# Core.net
KiCad netlist of a schematic drawn in Altium Designer
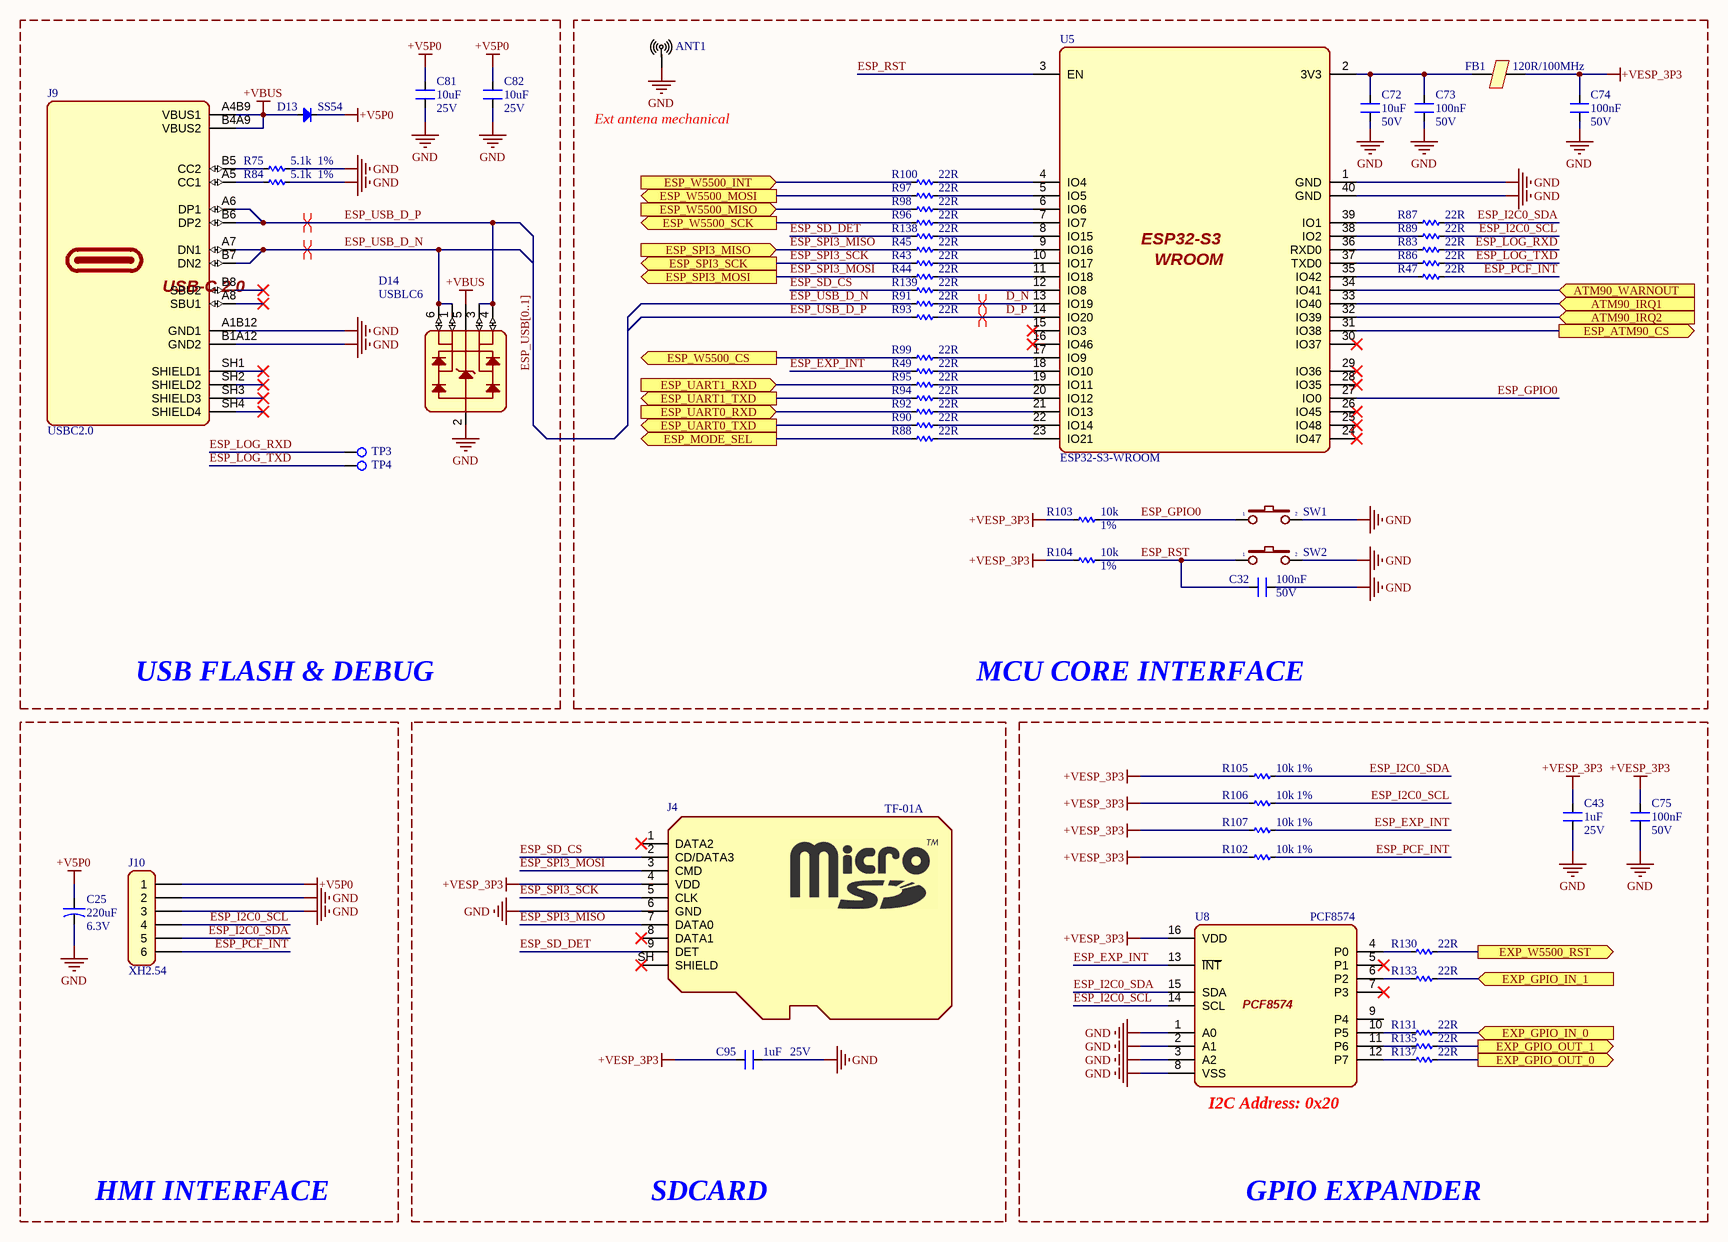
[diagram p0: Core.SchDoc]

(export (version "E")
  (design (tool "Eeschema 10.0.6"))
  (components
    (comp (ref "ANT1")
      (value "Anten")
      (footprint "Library_HUNG:SMA-8.5mm")
      (libsource (lib "Library_HUNG") (part "Anten Mechanical"))
    )
    (comp (ref "C25")
      (value "220uF")
      (footprint "TANT 2312")
      (fields (field (name "RATING") "6.3V"))
      (libsource (lib "Library_HUNG") (part "CN-TANTALUM"))
    )
    (comp (ref "C32")
      (value "100nF")
      (footprint "Library_HUNG:CAP_SMD_0603")
      (fields (field (name "RATING") "50V"))
      (libsource (lib "Library_HUNG") (part "CN"))
    )
    (comp (ref "C43")
      (value "1uF")
      (footprint "Library_HUNG:CAP_SMD_0603")
      (fields (field (name "RATING") "25V"))
      (libsource (lib "Library_HUNG") (part "CN"))
    )
    (comp (ref "C72")
      (value "10uF")
      (footprint "Library_HUNG:CAP_SMD_0805")
      (fields (field (name "RATING") "50V"))
      (libsource (lib "Library_HUNG") (part "CN"))
    )
    (comp (ref "C73")
      (value "100nF")
      (footprint "Library_HUNG:CAP_SMD_0805")
      (fields (field (name "RATING") "50V"))
      (libsource (lib "Library_HUNG") (part "CN"))
    )
    (comp (ref "C74")
      (value "100nF")
      (footprint "Library_HUNG:CAP_SMD_0805")
      (fields (field (name "RATING") "50V"))
      (libsource (lib "Library_HUNG") (part "CN"))
    )
    (comp (ref "C75")
      (value "100nF")
      (footprint "Library_HUNG:CAP_SMD_0603")
      (fields (field (name "RATING") "50V"))
      (libsource (lib "Library_HUNG") (part "CN"))
    )
    (comp (ref "C81")
      (value "10uF")
      (footprint "Library_HUNG:CAP_SMD_0603")
      (fields (field (name "RATING") "25V"))
      (libsource (lib "Library_HUNG") (part "CN"))
    )
    (comp (ref "C82")
      (value "10uF")
      (footprint "Library_HUNG:CAP_SMD_0603")
      (fields (field (name "RATING") "25V"))
      (libsource (lib "Library_HUNG") (part "CN"))
    )
    (comp (ref "C95")
      (value "1uF")
      (footprint "Library_HUNG:CAP_SMD_0603")
      (fields (field (name "RATING") "25V"))
      (libsource (lib "Library_HUNG") (part "CN"))
    )
    (comp (ref "D13")
      (value "SS54")
      (footprint "DIO-SMD-A")
      (description "Default Diode")
      (libsource (lib "Library_HUNG") (part "Diode SMD"))
    )
    (comp (ref "D14")
      (value "USBLC6")
      (footprint "Library_HUNG:SOT23-6")
      (description "TVS DIODE 5.25VWM 17VC SOT23-6")
      (libsource (lib "Library_HUNG") (part "USBLC6"))
    )
    (comp (ref "FB1")
      (value "120R/100MHz")
      (footprint "Ferrite-0805")
      (libsource (lib "Library_HUNG") (part "FERRITE BEAD"))
    )
    (comp (ref "J4")
      (value "TF-01A")
      (footprint "Library_HUNG:TF-01A")
      (libsource (lib "Library_HUNG") (part "SD_Socket"))
    )
    (comp (ref "J9")
      (value "USBC2.0")
      (footprint "Library_HUNG:MOLEX-2171790001")
      (description "USB Type C - Connector, Top-mount SMT, 16pos ¦ Molex Incorporated 217179-0001")
      (libsource (lib "Library_HUNG") (part "USBC-2.0"))
    )
    (comp (ref "J10")
      (value "XH2.54")
      (footprint "XH2.54-6P-TH")
      (libsource (lib "Library_HUNG") (part "Header6"))
    )
    (comp (ref "R43")
      (value "22R")
      (footprint "Library_HUNG:RES_SMD_0603")
      (description "Resistor")
      (fields (field (name "TOLERANCE") "1%"))
      (libsource (lib "Library_HUNG") (part "Res-SMD"))
    )
    (comp (ref "R44")
      (value "22R")
      (footprint "Library_HUNG:RES_SMD_0603")
      (description "Resistor")
      (fields (field (name "TOLERANCE") "1%"))
      (libsource (lib "Library_HUNG") (part "Res-SMD"))
    )
    (comp (ref "R45")
      (value "22R")
      (footprint "Library_HUNG:RES_SMD_0603")
      (description "Resistor")
      (fields (field (name "TOLERANCE") "1%"))
      (libsource (lib "Library_HUNG") (part "Res-SMD"))
    )
    (comp (ref "R47")
      (value "22R")
      (footprint "Library_HUNG:RES_SMD_0603")
      (description "Resistor")
      (fields (field (name "TOLERANCE") "1%"))
      (libsource (lib "Library_HUNG") (part "Res-SMD"))
    )
    (comp (ref "R49")
      (value "22R")
      (footprint "Library_HUNG:RES_SMD_0603")
      (description "Resistor")
      (fields (field (name "TOLERANCE") "1%"))
      (libsource (lib "Library_HUNG") (part "Res-SMD"))
    )
    (comp (ref "R75")
      (value "5.1k")
      (footprint "Library_HUNG:RES_SMD_0603")
      (description "Resistor")
      (fields (field (name "TOLERANCE") "1%"))
      (libsource (lib "Library_HUNG") (part "Res-SMD"))
    )
    (comp (ref "R83")
      (value "22R")
      (footprint "Library_HUNG:RES_SMD_0603")
      (description "Resistor")
      (fields (field (name "TOLERANCE") "1%"))
      (libsource (lib "Library_HUNG") (part "Res-SMD"))
    )
    (comp (ref "R84")
      (value "5.1k")
      (footprint "Library_HUNG:RES_SMD_0603")
      (description "Resistor")
      (fields (field (name "TOLERANCE") "1%"))
      (libsource (lib "Library_HUNG") (part "Res-SMD"))
    )
    (comp (ref "R86")
      (value "22R")
      (footprint "Library_HUNG:RES_SMD_0603")
      (description "Resistor")
      (fields (field (name "TOLERANCE") "1%"))
      (libsource (lib "Library_HUNG") (part "Res-SMD"))
    )
    (comp (ref "R87")
      (value "22R")
      (footprint "Library_HUNG:RES_SMD_0603")
      (description "Resistor")
      (fields (field (name "TOLERANCE") "1%"))
      (libsource (lib "Library_HUNG") (part "Res-SMD"))
    )
    (comp (ref "R88")
      (value "22R")
      (footprint "Library_HUNG:RES_SMD_0603")
      (description "Resistor")
      (fields (field (name "TOLERANCE") "1%"))
      (libsource (lib "Library_HUNG") (part "Res-SMD"))
    )
    (comp (ref "R89")
      (value "22R")
      (footprint "Library_HUNG:RES_SMD_0603")
      (description "Resistor")
      (fields (field (name "TOLERANCE") "1%"))
      (libsource (lib "Library_HUNG") (part "Res-SMD"))
    )
    (comp (ref "R90")
      (value "22R")
      (footprint "Library_HUNG:RES_SMD_0603")
      (description "Resistor")
      (fields (field (name "TOLERANCE") "1%"))
      (libsource (lib "Library_HUNG") (part "Res-SMD"))
    )
    (comp (ref "R91")
      (value "22R")
      (footprint "Library_HUNG:RES_SMD_0603")
      (description "Resistor")
      (fields (field (name "TOLERANCE") "1%"))
      (libsource (lib "Library_HUNG") (part "Res-SMD"))
    )
    (comp (ref "R92")
      (value "22R")
      (footprint "Library_HUNG:RES_SMD_0603")
      (description "Resistor")
      (fields (field (name "TOLERANCE") "1%"))
      (libsource (lib "Library_HUNG") (part "Res-SMD"))
    )
    (comp (ref "R93")
      (value "22R")
      (footprint "Library_HUNG:RES_SMD_0603")
      (description "Resistor")
      (fields (field (name "TOLERANCE") "1%"))
      (libsource (lib "Library_HUNG") (part "Res-SMD"))
    )
    (comp (ref "R94")
      (value "22R")
      (footprint "Library_HUNG:RES_SMD_0603")
      (description "Resistor")
      (fields (field (name "TOLERANCE") "1%"))
      (libsource (lib "Library_HUNG") (part "Res-SMD"))
    )
    (comp (ref "R95")
      (value "22R")
      (footprint "Library_HUNG:RES_SMD_0603")
      (description "Resistor")
      (fields (field (name "TOLERANCE") "1%"))
      (libsource (lib "Library_HUNG") (part "Res-SMD"))
    )
    (comp (ref "R96")
      (value "22R")
      (footprint "Library_HUNG:RES_SMD_0603")
      (description "Resistor")
      (fields (field (name "TOLERANCE") "1%"))
      (libsource (lib "Library_HUNG") (part "Res-SMD"))
    )
    (comp (ref "R97")
      (value "22R")
      (footprint "Library_HUNG:RES_SMD_0603")
      (description "Resistor")
      (fields (field (name "TOLERANCE") "1%"))
      (libsource (lib "Library_HUNG") (part "Res-SMD"))
    )
    (comp (ref "R98")
      (value "22R")
      (footprint "Library_HUNG:RES_SMD_0603")
      (description "Resistor")
      (fields (field (name "TOLERANCE") "1%"))
      (libsource (lib "Library_HUNG") (part "Res-SMD"))
    )
    (comp (ref "R99")
      (value "22R")
      (footprint "Library_HUNG:RES_SMD_0603")
      (description "Resistor")
      (fields (field (name "TOLERANCE") "1%"))
      (libsource (lib "Library_HUNG") (part "Res-SMD"))
    )
    (comp (ref "R100")
      (value "22R")
      (footprint "Library_HUNG:RES_SMD_0603")
      (description "Resistor")
      (fields (field (name "TOLERANCE") "1%"))
      (libsource (lib "Library_HUNG") (part "Res-SMD"))
    )
    (comp (ref "R102")
      (value "10k")
      (footprint "Library_HUNG:RES_SMD_0603")
      (description "Resistor")
      (fields (field (name "TOLERANCE") "1%"))
      (libsource (lib "Library_HUNG") (part "Res-SMD"))
    )
    (comp (ref "R103")
      (value "10k")
      (footprint "Library_HUNG:RES_SMD_0603")
      (description "Resistor")
      (fields (field (name "TOLERANCE") "1%"))
      (libsource (lib "Library_HUNG") (part "Res-SMD"))
    )
    (comp (ref "R104")
      (value "10k")
      (footprint "Library_HUNG:RES_SMD_0603")
      (description "Resistor")
      (fields (field (name "TOLERANCE") "1%"))
      (libsource (lib "Library_HUNG") (part "Res-SMD"))
    )
    (comp (ref "R105")
      (value "10k")
      (footprint "Library_HUNG:RES_SMD_0603")
      (description "Resistor")
      (fields (field (name "TOLERANCE") "1%"))
      (libsource (lib "Library_HUNG") (part "Res-SMD"))
    )
    (comp (ref "R106")
      (value "10k")
      (footprint "Library_HUNG:RES_SMD_0603")
      (description "Resistor")
      (fields (field (name "TOLERANCE") "1%"))
      (libsource (lib "Library_HUNG") (part "Res-SMD"))
    )
    (comp (ref "R107")
      (value "10k")
      (footprint "Library_HUNG:RES_SMD_0603")
      (description "Resistor")
      (fields (field (name "TOLERANCE") "1%"))
      (libsource (lib "Library_HUNG") (part "Res-SMD"))
    )
    (comp (ref "R130")
      (value "22R")
      (footprint "Library_HUNG:RES_SMD_0603")
      (description "Resistor")
      (fields (field (name "TOLERANCE") "1%"))
      (libsource (lib "Library_HUNG") (part "Res-SMD"))
    )
    (comp (ref "R131")
      (value "22R")
      (footprint "Library_HUNG:RES_SMD_0603")
      (description "Resistor")
      (fields (field (name "TOLERANCE") "1%"))
      (libsource (lib "Library_HUNG") (part "Res-SMD"))
    )
    (comp (ref "R133")
      (value "22R")
      (footprint "Library_HUNG:RES_SMD_0603")
      (description "Resistor")
      (fields (field (name "TOLERANCE") "1%"))
      (libsource (lib "Library_HUNG") (part "Res-SMD"))
    )
    (comp (ref "R135")
      (value "22R")
      (footprint "Library_HUNG:RES_SMD_0603")
      (description "Resistor")
      (fields (field (name "TOLERANCE") "1%"))
      (libsource (lib "Library_HUNG") (part "Res-SMD"))
    )
    (comp (ref "R137")
      (value "22R")
      (footprint "Library_HUNG:RES_SMD_0603")
      (description "Resistor")
      (fields (field (name "TOLERANCE") "1%"))
      (libsource (lib "Library_HUNG") (part "Res-SMD"))
    )
    (comp (ref "R138")
      (value "22R")
      (footprint "Library_HUNG:RES_SMD_0603")
      (description "Resistor")
      (fields (field (name "TOLERANCE") "1%"))
      (libsource (lib "Library_HUNG") (part "Res-SMD"))
    )
    (comp (ref "R139")
      (value "22R")
      (footprint "Library_HUNG:RES_SMD_0603")
      (description "Resistor")
      (fields (field (name "TOLERANCE") "1%"))
      (libsource (lib "Library_HUNG") (part "Res-SMD"))
    )
    (comp (ref "SW1")
      (value "SW2")
      (footprint "SW1-SMD")
      (description "Switch button 2 pin")
      (libsource (lib "Library_HUNG") (part "SW2"))
    )
    (comp (ref "SW2")
      (value "SW2")
      (footprint "SW2-r-6x6mm")
      (description "Switch button 2 pin")
      (libsource (lib "Library_HUNG") (part "SW2"))
    )
    (comp (ref "TP3")
      (value "Test_Point")
      (footprint "PAD-SMD-D2.0")
      (libsource (lib "Library_HUNG") (part "Test_Point"))
    )
    (comp (ref "TP4")
      (value "Test_Point")
      (footprint "PAD-SMD-D2.0")
      (libsource (lib "Library_HUNG") (part "Test_Point"))
    )
    (comp (ref "U5")
      (value "ESP32-S3-WROOM")
      (footprint "ESP32-S3-WROOM-1U-N16R8")
      (libsource (lib "Library_HUNG") (part "ESP32-S3-WROOM"))
    )
    (comp (ref "U8")
      (value "PCF8574")
      (footprint "SOIC-16-300mil")
      (libsource (lib "Library_HUNG") (part "PCF8574"))
    )
  )
  (nets
    (net (code "3") (name "+V5P0") (class "Default")
      (node (ref "C25") (pin "1") (pinfunction "1_1") (pintype "passive"))
      (node (ref "C81") (pin "1") (pinfunction "1_1") (pintype "passive"))
      (node (ref "C82") (pin "1") (pinfunction "1_1") (pintype "passive"))
      (node (ref "D13") (pin "2") (pinfunction "K_2") (pintype "passive"))
      (node (ref "J10") (pin "1") (pinfunction "1_1") (pintype "passive"))
    )
    (net (code "4") (name "+VBUS") (class "Default")
      (node (ref "D13") (pin "1") (pinfunction "A_1") (pintype "passive"))
      (node (ref "D14") (pin "5") (pinfunction "VBUS_5") (pintype "power_in"))
      (node (ref "J9") (pin "A4B9") (pinfunction "VBUS1_A4B9") (pintype "power_in"))
      (node (ref "J9") (pin "B4A9") (pinfunction "VBUS2_B4A9") (pintype "power_in"))
    )
    (net (code "5") (name "+VESP_3P3") (class "Default")
      (node (ref "C43") (pin "1") (pinfunction "1_1") (pintype "passive"))
      (node (ref "C74") (pin "1") (pinfunction "1_1") (pintype "passive"))
      (node (ref "C75") (pin "1") (pinfunction "1_1") (pintype "passive"))
      (node (ref "C95") (pin "1") (pinfunction "1_1") (pintype "passive"))
      (node (ref "FB1") (pin "2") (pintype "passive"))
      (node (ref "J4") (pin "4") (pinfunction "VDD_4") (pintype "passive"))
      (node (ref "R102") (pin "1") (pinfunction "1_1") (pintype "passive"))
      (node (ref "R103") (pin "1") (pinfunction "1_1") (pintype "passive"))
      (node (ref "R104") (pin "1") (pinfunction "1_1") (pintype "passive"))
      (node (ref "R105") (pin "1") (pinfunction "1_1") (pintype "passive"))
      (node (ref "R106") (pin "1") (pinfunction "1_1") (pintype "passive"))
      (node (ref "R107") (pin "1") (pinfunction "1_1") (pintype "passive"))
      (node (ref "U8") (pin "16") (pinfunction "VDD_16") (pintype "passive"))
    )
    (net (code "6") (name "/ATM90_IRQ1") (class "Default")
      (node (ref "U5") (pin "33") (pinfunction "IO40_33") (pintype "passive"))
    )
    (net (code "7") (name "/ATM90_IRQ2") (class "Default")
      (node (ref "U5") (pin "32") (pinfunction "IO39_32") (pintype "passive"))
    )
    (net (code "8") (name "/ATM90_WARNOUT") (class "Default")
      (node (ref "U5") (pin "34") (pinfunction "IO41_34") (pintype "passive"))
    )
    (net (code "9") (name "/D_N") (class "Default")
      (node (ref "R91") (pin "1") (pinfunction "1_1") (pintype "passive"))
      (node (ref "U5") (pin "13") (pinfunction "IO19_13") (pintype "passive"))
    )
    (net (code "10") (name "/D_P") (class "Default")
      (node (ref "R93") (pin "1") (pinfunction "1_1") (pintype "passive"))
      (node (ref "U5") (pin "14") (pinfunction "IO20_14") (pintype "passive"))
    )
    (net (code "11") (name "/ESP_ATM90_CS") (class "Default")
      (node (ref "U5") (pin "31") (pinfunction "IO38_31") (pintype "passive"))
    )
    (net (code "12") (name "/ESP_EXP_INT") (class "Default")
      (node (ref "R107") (pin "2") (pinfunction "2_2") (pintype "passive"))
      (node (ref "R49") (pin "2") (pinfunction "2_2") (pintype "passive"))
      (node (ref "U8") (pin "13") (pinfunction "~{INT}_13") (pintype "passive"))
    )
    (net (code "13") (name "/ESP_GPIO0") (class "Default")
      (node (ref "R103") (pin "2") (pinfunction "2_2") (pintype "passive"))
      (node (ref "SW1") (pin "1") (pinfunction "1_1") (pintype "passive"))
      (node (ref "U5") (pin "27") (pinfunction "IO0_27") (pintype "passive"))
    )
    (net (code "14") (name "/ESP_I2C0_SCL") (class "Default")
      (node (ref "J10") (pin "4") (pinfunction "4_4") (pintype "passive"))
      (node (ref "R106") (pin "2") (pinfunction "2_2") (pintype "passive"))
      (node (ref "R89") (pin "1") (pinfunction "1_1") (pintype "passive"))
      (node (ref "U8") (pin "14") (pinfunction "SCL_14") (pintype "passive"))
    )
    (net (code "15") (name "/ESP_I2C0_SDA") (class "Default")
      (node (ref "J10") (pin "5") (pinfunction "5_5") (pintype "passive"))
      (node (ref "R105") (pin "2") (pinfunction "2_2") (pintype "passive"))
      (node (ref "R87") (pin "1") (pinfunction "1_1") (pintype "passive"))
      (node (ref "U8") (pin "15") (pinfunction "SDA_15") (pintype "passive"))
    )
    (net (code "16") (name "/ESP_LOG_RXD") (class "Default")
      (node (ref "R83") (pin "1") (pinfunction "1_1") (pintype "passive"))
      (node (ref "TP3") (pin "1") (pintype "passive"))
    )
    (net (code "17") (name "/ESP_LOG_TXD") (class "Default")
      (node (ref "R86") (pin "1") (pinfunction "1_1") (pintype "passive"))
      (node (ref "TP4") (pin "1") (pintype "passive"))
    )
    (net (code "18") (name "/ESP_MODE_SEL") (class "Default")
      (node (ref "R88") (pin "1") (pinfunction "1_1") (pintype "passive"))
    )
    (net (code "19") (name "/ESP_PCF_INT") (class "Default")
      (node (ref "J10") (pin "6") (pinfunction "6_6") (pintype "passive"))
      (node (ref "R102") (pin "2") (pinfunction "2_2") (pintype "passive"))
      (node (ref "R47") (pin "1") (pinfunction "1_1") (pintype "passive"))
    )
    (net (code "20") (name "/ESP_RST") (class "Default")
      (node (ref "C32") (pin "2") (pinfunction "2_2") (pintype "passive"))
      (node (ref "R104") (pin "2") (pinfunction "2_2") (pintype "passive"))
      (node (ref "SW2") (pin "1") (pinfunction "1_1") (pintype "passive"))
      (node (ref "U5") (pin "3") (pinfunction "EN_3") (pintype "passive"))
    )
    (net (code "21") (name "/ESP_SD_CS") (class "Default")
      (node (ref "J4") (pin "2") (pinfunction "CD/DATA3_2") (pintype "passive"))
      (node (ref "R139") (pin "2") (pinfunction "2_2") (pintype "passive"))
    )
    (net (code "22") (name "/ESP_SD_DET") (class "Default")
      (node (ref "J4") (pin "9") (pinfunction "DET_9") (pintype "passive"))
      (node (ref "R138") (pin "2") (pinfunction "2_2") (pintype "passive"))
    )
    (net (code "23") (name "/ESP_SPI3_MISO") (class "Default")
      (node (ref "J4") (pin "7") (pinfunction "DATA0_7") (pintype "passive"))
      (node (ref "R45") (pin "2") (pinfunction "2_2") (pintype "passive"))
    )
    (net (code "24") (name "/ESP_SPI3_MOSI") (class "Default")
      (node (ref "J4") (pin "3") (pinfunction "CMD_3") (pintype "passive"))
      (node (ref "R44") (pin "2") (pinfunction "2_2") (pintype "passive"))
    )
    (net (code "25") (name "/ESP_SPI3_SCK") (class "Default")
      (node (ref "J4") (pin "5") (pinfunction "CLK_5") (pintype "passive"))
      (node (ref "R43") (pin "2") (pinfunction "2_2") (pintype "passive"))
    )
    (net (code "26") (name "/ESP_UART0_RXD") (class "Default")
      (node (ref "R92") (pin "1") (pinfunction "1_1") (pintype "passive"))
    )
    (net (code "27") (name "/ESP_UART0_TXD") (class "Default")
      (node (ref "R90") (pin "1") (pinfunction "1_1") (pintype "passive"))
    )
    (net (code "28") (name "/ESP_UART1_RXD") (class "Default")
      (node (ref "R95") (pin "1") (pinfunction "1_1") (pintype "passive"))
    )
    (net (code "29") (name "/ESP_UART1_TXD") (class "Default")
      (node (ref "R94") (pin "1") (pinfunction "1_1") (pintype "passive"))
    )
    (net (code "31") (name "/ESP_USB_D_N") (class "Default")
      (node (ref "D14") (pin "1") (pinfunction "I/O1_IN_1") (pintype "bidirectional"))
      (node (ref "D14") (pin "6") (pinfunction "I/O1_OUT_6") (pintype "bidirectional"))
      (node (ref "J9") (pin "A7") (pinfunction "DN1_A7") (pintype "bidirectional"))
      (node (ref "J9") (pin "B7") (pinfunction "DN2_B7") (pintype "bidirectional"))
      (node (ref "R91") (pin "2") (pinfunction "2_2") (pintype "passive"))
    )
    (net (code "32") (name "/ESP_USB_D_P") (class "Default")
      (node (ref "D14") (pin "3") (pinfunction "I/O2_IN_3") (pintype "bidirectional"))
      (node (ref "D14") (pin "4") (pinfunction "I/O2_OUT_4") (pintype "bidirectional"))
      (node (ref "J9") (pin "A6") (pinfunction "DP1_A6") (pintype "bidirectional"))
      (node (ref "J9") (pin "B6") (pinfunction "DP2_B6") (pintype "bidirectional"))
      (node (ref "R93") (pin "2") (pinfunction "2_2") (pintype "passive"))
    )
    (net (code "33") (name "/ESP_W5500_CS") (class "Default")
      (node (ref "R99") (pin "2") (pinfunction "2_2") (pintype "passive"))
    )
    (net (code "34") (name "/ESP_W5500_INT") (class "Default")
      (node (ref "R100") (pin "2") (pinfunction "2_2") (pintype "passive"))
    )
    (net (code "35") (name "/ESP_W5500_MISO") (class "Default")
      (node (ref "R98") (pin "2") (pinfunction "2_2") (pintype "passive"))
    )
    (net (code "36") (name "/ESP_W5500_MOSI") (class "Default")
      (node (ref "R97") (pin "2") (pinfunction "2_2") (pintype "passive"))
    )
    (net (code "37") (name "/ESP_W5500_SCK") (class "Default")
      (node (ref "R96") (pin "2") (pinfunction "2_2") (pintype "passive"))
    )
    (net (code "38") (name "/EXP_GPIO_IN_0") (class "Default")
      (node (ref "R131") (pin "1") (pinfunction "1_1") (pintype "passive"))
    )
    (net (code "39") (name "/EXP_GPIO_IN_1") (class "Default")
      (node (ref "R133") (pin "1") (pinfunction "1_1") (pintype "passive"))
    )
    (net (code "40") (name "/EXP_GPIO_OUT_0") (class "Default")
      (node (ref "R137") (pin "1") (pinfunction "1_1") (pintype "passive"))
    )
    (net (code "41") (name "/EXP_GPIO_OUT_1") (class "Default")
      (node (ref "R135") (pin "1") (pinfunction "1_1") (pintype "passive"))
    )
    (net (code "42") (name "/EXP_W5500_RST") (class "Default")
      (node (ref "R130") (pin "1") (pinfunction "1_1") (pintype "passive"))
    )
    (net (code "43") (name "GND") (class "Default")
      (node (ref "ANT1") (pin "MP") (pinfunction "GND_MP") (pintype "passive"))
      (node (ref "C25") (pin "2") (pinfunction "2_2") (pintype "passive"))
      (node (ref "C32") (pin "1") (pinfunction "1_1") (pintype "passive"))
      (node (ref "C43") (pin "2") (pinfunction "2_2") (pintype "passive"))
      (node (ref "C72") (pin "2") (pinfunction "2_2") (pintype "passive"))
      (node (ref "C73") (pin "2") (pinfunction "2_2") (pintype "passive"))
      (node (ref "C74") (pin "2") (pinfunction "2_2") (pintype "passive"))
      (node (ref "C75") (pin "2") (pinfunction "2_2") (pintype "passive"))
      (node (ref "C81") (pin "2") (pinfunction "2_2") (pintype "passive"))
      (node (ref "C82") (pin "2") (pinfunction "2_2") (pintype "passive"))
      (node (ref "C95") (pin "2") (pinfunction "2_2") (pintype "passive"))
      (node (ref "D14") (pin "2") (pinfunction "GND_2") (pintype "power_in"))
      (node (ref "J10") (pin "2") (pinfunction "2_2") (pintype "passive"))
      (node (ref "J10") (pin "3") (pinfunction "3_3") (pintype "passive"))
      (node (ref "J4") (pin "6") (pinfunction "GND_6") (pintype "passive"))
      (node (ref "J9") (pin "A1B12") (pinfunction "GND1_A1B12") (pintype "power_in"))
      (node (ref "J9") (pin "B1A12") (pinfunction "GND2_B1A12") (pintype "power_in"))
      (node (ref "R75") (pin "2") (pinfunction "2_2") (pintype "passive"))
      (node (ref "R84") (pin "2") (pinfunction "2_2") (pintype "passive"))
      (node (ref "SW1") (pin "2") (pinfunction "2_2") (pintype "passive"))
      (node (ref "SW2") (pin "2") (pinfunction "2_2") (pintype "passive"))
      (node (ref "U5") (pin "1") (pinfunction "GND_1") (pintype "power_in"))
      (node (ref "U5") (pin "40") (pinfunction "GND_40") (pintype "power_in"))
      (node (ref "U8") (pin "1") (pinfunction "A0_1") (pintype "passive"))
      (node (ref "U8") (pin "2") (pinfunction "A1_2") (pintype "passive"))
      (node (ref "U8") (pin "3") (pinfunction "A2_3") (pintype "passive"))
      (node (ref "U8") (pin "8") (pinfunction "VSS_8") (pintype "passive"))
    )
    (net (code "44") (name "Net-(J9-CC1)") (class "Default")
      (node (ref "J9") (pin "A5") (pinfunction "CC1_A5") (pintype "bidirectional"))
      (node (ref "R84") (pin "1") (pinfunction "1_1") (pintype "passive"))
    )
    (net (code "45") (name "Net-(J9-CC2)") (class "Default")
      (node (ref "J9") (pin "B5") (pinfunction "CC2_B5") (pintype "bidirectional"))
      (node (ref "R75") (pin "1") (pinfunction "1_1") (pintype "passive"))
    )
    (net (code "46") (name "Net-(U5-3V3)") (class "Default")
      (node (ref "C72") (pin "1") (pinfunction "1_1") (pintype "passive"))
      (node (ref "C73") (pin "1") (pinfunction "1_1") (pintype "passive"))
      (node (ref "FB1") (pin "1") (pintype "passive"))
      (node (ref "U5") (pin "2") (pinfunction "3V3_2") (pintype "power_in"))
    )
    (net (code "47") (name "Net-(U5-IO1)") (class "Default")
      (node (ref "R87") (pin "2") (pinfunction "2_2") (pintype "passive"))
      (node (ref "U5") (pin "39") (pinfunction "IO1_39") (pintype "passive"))
    )
    (net (code "48") (name "Net-(U5-IO2)") (class "Default")
      (node (ref "R89") (pin "2") (pinfunction "2_2") (pintype "passive"))
      (node (ref "U5") (pin "38") (pinfunction "IO2_38") (pintype "passive"))
    )
    (net (code "49") (name "Net-(U5-IO4)") (class "Default")
      (node (ref "R100") (pin "1") (pinfunction "1_1") (pintype "passive"))
      (node (ref "U5") (pin "4") (pinfunction "IO4_4") (pintype "passive"))
    )
    (net (code "50") (name "Net-(U5-IO5)") (class "Default")
      (node (ref "R97") (pin "1") (pinfunction "1_1") (pintype "passive"))
      (node (ref "U5") (pin "5") (pinfunction "IO5_5") (pintype "passive"))
    )
    (net (code "51") (name "Net-(U5-IO6)") (class "Default")
      (node (ref "R98") (pin "1") (pinfunction "1_1") (pintype "passive"))
      (node (ref "U5") (pin "6") (pinfunction "IO6_6") (pintype "passive"))
    )
    (net (code "52") (name "Net-(U5-IO7)") (class "Default")
      (node (ref "R96") (pin "1") (pinfunction "1_1") (pintype "passive"))
      (node (ref "U5") (pin "7") (pinfunction "IO7_7") (pintype "passive"))
    )
    (net (code "53") (name "Net-(U5-IO8)") (class "Default")
      (node (ref "R139") (pin "1") (pinfunction "1_1") (pintype "passive"))
      (node (ref "U5") (pin "12") (pinfunction "IO8_12") (pintype "passive"))
    )
    (net (code "54") (name "Net-(U5-IO9)") (class "Default")
      (node (ref "R99") (pin "1") (pinfunction "1_1") (pintype "passive"))
      (node (ref "U5") (pin "17") (pinfunction "IO9_17") (pintype "passive"))
    )
    (net (code "55") (name "Net-(U5-IO10)") (class "Default")
      (node (ref "R49") (pin "1") (pinfunction "1_1") (pintype "passive"))
      (node (ref "U5") (pin "18") (pinfunction "IO10_18") (pintype "passive"))
    )
    (net (code "56") (name "Net-(U5-IO11)") (class "Default")
      (node (ref "R95") (pin "2") (pinfunction "2_2") (pintype "passive"))
      (node (ref "U5") (pin "19") (pinfunction "IO11_19") (pintype "passive"))
    )
    (net (code "57") (name "Net-(U5-IO12)") (class "Default")
      (node (ref "R94") (pin "2") (pinfunction "2_2") (pintype "passive"))
      (node (ref "U5") (pin "20") (pinfunction "IO12_20") (pintype "passive"))
    )
    (net (code "58") (name "Net-(U5-IO13)") (class "Default")
      (node (ref "R92") (pin "2") (pinfunction "2_2") (pintype "passive"))
      (node (ref "U5") (pin "21") (pinfunction "IO13_21") (pintype "passive"))
    )
    (net (code "59") (name "Net-(U5-IO14)") (class "Default")
      (node (ref "R90") (pin "2") (pinfunction "2_2") (pintype "passive"))
      (node (ref "U5") (pin "22") (pinfunction "IO14_22") (pintype "passive"))
    )
    (net (code "60") (name "Net-(U5-IO15)") (class "Default")
      (node (ref "R138") (pin "1") (pinfunction "1_1") (pintype "passive"))
      (node (ref "U5") (pin "8") (pinfunction "IO15_8") (pintype "passive"))
    )
    (net (code "61") (name "Net-(U5-IO16)") (class "Default")
      (node (ref "R45") (pin "1") (pinfunction "1_1") (pintype "passive"))
      (node (ref "U5") (pin "9") (pinfunction "IO16_9") (pintype "passive"))
    )
    (net (code "62") (name "Net-(U5-IO17)") (class "Default")
      (node (ref "R43") (pin "1") (pinfunction "1_1") (pintype "passive"))
      (node (ref "U5") (pin "10") (pinfunction "IO17_10") (pintype "passive"))
    )
    (net (code "63") (name "Net-(U5-IO18)") (class "Default")
      (node (ref "R44") (pin "1") (pinfunction "1_1") (pintype "passive"))
      (node (ref "U5") (pin "11") (pinfunction "IO18_11") (pintype "passive"))
    )
    (net (code "64") (name "Net-(U5-IO21)") (class "Default")
      (node (ref "R88") (pin "2") (pinfunction "2_2") (pintype "passive"))
      (node (ref "U5") (pin "23") (pinfunction "IO21_23") (pintype "passive"))
    )
    (net (code "65") (name "Net-(U5-IO42)") (class "Default")
      (node (ref "R47") (pin "2") (pinfunction "2_2") (pintype "passive"))
      (node (ref "U5") (pin "35") (pinfunction "IO42_35") (pintype "passive"))
    )
    (net (code "66") (name "Net-(U5-RXD0)") (class "Default")
      (node (ref "R83") (pin "2") (pinfunction "2_2") (pintype "passive"))
      (node (ref "U5") (pin "36") (pinfunction "RXD0_36") (pintype "passive"))
    )
    (net (code "67") (name "Net-(U5-TXD0)") (class "Default")
      (node (ref "R86") (pin "2") (pinfunction "2_2") (pintype "passive"))
      (node (ref "U5") (pin "37") (pinfunction "TXD0_37") (pintype "passive"))
    )
    (net (code "68") (name "Net-(U8-P0)") (class "Default")
      (node (ref "R130") (pin "2") (pinfunction "2_2") (pintype "passive"))
      (node (ref "U8") (pin "4") (pinfunction "P0_4") (pintype "passive"))
    )
    (net (code "69") (name "Net-(U8-P2)") (class "Default")
      (node (ref "R133") (pin "2") (pinfunction "2_2") (pintype "passive"))
      (node (ref "U8") (pin "6") (pinfunction "P2_6") (pintype "passive"))
    )
    (net (code "70") (name "Net-(U8-P5)") (class "Default")
      (node (ref "R131") (pin "2") (pinfunction "2_2") (pintype "passive"))
      (node (ref "U8") (pin "10") (pinfunction "P5_10") (pintype "passive"))
    )
    (net (code "71") (name "Net-(U8-P6)") (class "Default")
      (node (ref "R135") (pin "2") (pinfunction "2_2") (pintype "passive"))
      (node (ref "U8") (pin "11") (pinfunction "P6_11") (pintype "passive"))
    )
    (net (code "72") (name "Net-(U8-P7)") (class "Default")
      (node (ref "R137") (pin "2") (pinfunction "2_2") (pintype "passive"))
      (node (ref "U8") (pin "12") (pinfunction "P7_12") (pintype "passive"))
    )
    (net (code "73") (name "unconnected-(J4-DATA1-Pad8)") (class "Default")
      (node (ref "J4") (pin "8") (pinfunction "DATA1_8") (pintype "passive+no_connect"))
    )
    (net (code "74") (name "unconnected-(J4-DATA2-Pad1)") (class "Default")
      (node (ref "J4") (pin "1") (pinfunction "DATA2_1") (pintype "passive+no_connect"))
    )
    (net (code "75") (name "unconnected-(J4-SHIELD-PadSH)") (class "Default")
      (node (ref "J4") (pin "SH") (pinfunction "SHIELD_SH") (pintype "passive+no_connect"))
    )
    (net (code "76") (name "unconnected-(J9-SBU1-PadA8)") (class "Default")
      (node (ref "J9") (pin "A8") (pinfunction "SBU1_A8") (pintype "bidirectional+no_connect"))
    )
    (net (code "77") (name "unconnected-(J9-SBU2-PadB8)") (class "Default")
      (node (ref "J9") (pin "B8") (pinfunction "SBU2_B8") (pintype "bidirectional+no_connect"))
    )
    (net (code "78") (name "unconnected-(J9-SHIELD1-PadSH1)") (class "Default")
      (node (ref "J9") (pin "SH1") (pinfunction "SHIELD1_SH1") (pintype "passive+no_connect"))
    )
    (net (code "79") (name "unconnected-(J9-SHIELD2-PadSH2)") (class "Default")
      (node (ref "J9") (pin "SH2") (pinfunction "SHIELD2_SH2") (pintype "passive+no_connect"))
    )
    (net (code "80") (name "unconnected-(J9-SHIELD3-PadSH3)") (class "Default")
      (node (ref "J9") (pin "SH3") (pinfunction "SHIELD3_SH3") (pintype "passive+no_connect"))
    )
    (net (code "81") (name "unconnected-(J9-SHIELD4-PadSH4)") (class "Default")
      (node (ref "J9") (pin "SH4") (pinfunction "SHIELD4_SH4") (pintype "passive+no_connect"))
    )
    (net (code "82") (name "unconnected-(U5-IO3-Pad15)") (class "Default")
      (node (ref "U5") (pin "15") (pinfunction "IO3_15") (pintype "passive+no_connect"))
    )
    (net (code "83") (name "unconnected-(U5-IO35-Pad28)") (class "Default")
      (node (ref "U5") (pin "28") (pinfunction "IO35_28") (pintype "passive+no_connect"))
    )
    (net (code "84") (name "unconnected-(U5-IO36-Pad29)") (class "Default")
      (node (ref "U5") (pin "29") (pinfunction "IO36_29") (pintype "passive+no_connect"))
    )
    (net (code "85") (name "unconnected-(U5-IO37-Pad30)") (class "Default")
      (node (ref "U5") (pin "30") (pinfunction "IO37_30") (pintype "passive+no_connect"))
    )
    (net (code "86") (name "unconnected-(U5-IO45-Pad26)") (class "Default")
      (node (ref "U5") (pin "26") (pinfunction "IO45_26") (pintype "passive+no_connect"))
    )
    (net (code "87") (name "unconnected-(U5-IO46-Pad16)") (class "Default")
      (node (ref "U5") (pin "16") (pinfunction "IO46_16") (pintype "passive+no_connect"))
    )
    (net (code "88") (name "unconnected-(U5-IO47-Pad24)") (class "Default")
      (node (ref "U5") (pin "24") (pinfunction "IO47_24") (pintype "passive+no_connect"))
    )
    (net (code "89") (name "unconnected-(U5-IO48-Pad25)") (class "Default")
      (node (ref "U5") (pin "25") (pinfunction "IO48_25") (pintype "passive+no_connect"))
    )
    (net (code "90") (name "unconnected-(U8-P1-Pad5)") (class "Default")
      (node (ref "U8") (pin "5") (pinfunction "P1_5") (pintype "passive+no_connect"))
    )
    (net (code "91") (name "unconnected-(U8-P3-Pad7)") (class "Default")
      (node (ref "U8") (pin "7") (pinfunction "P3_7") (pintype "passive+no_connect"))
    )
    (net (code "92") (name "unconnected-(U8-P4-Pad9)") (class "Default")
      (node (ref "U8") (pin "9") (pinfunction "P4_9") (pintype "passive"))
    )
  )
)
